# dual_sampler.net
KiCad netlist of a schematic drawn in EAGLE
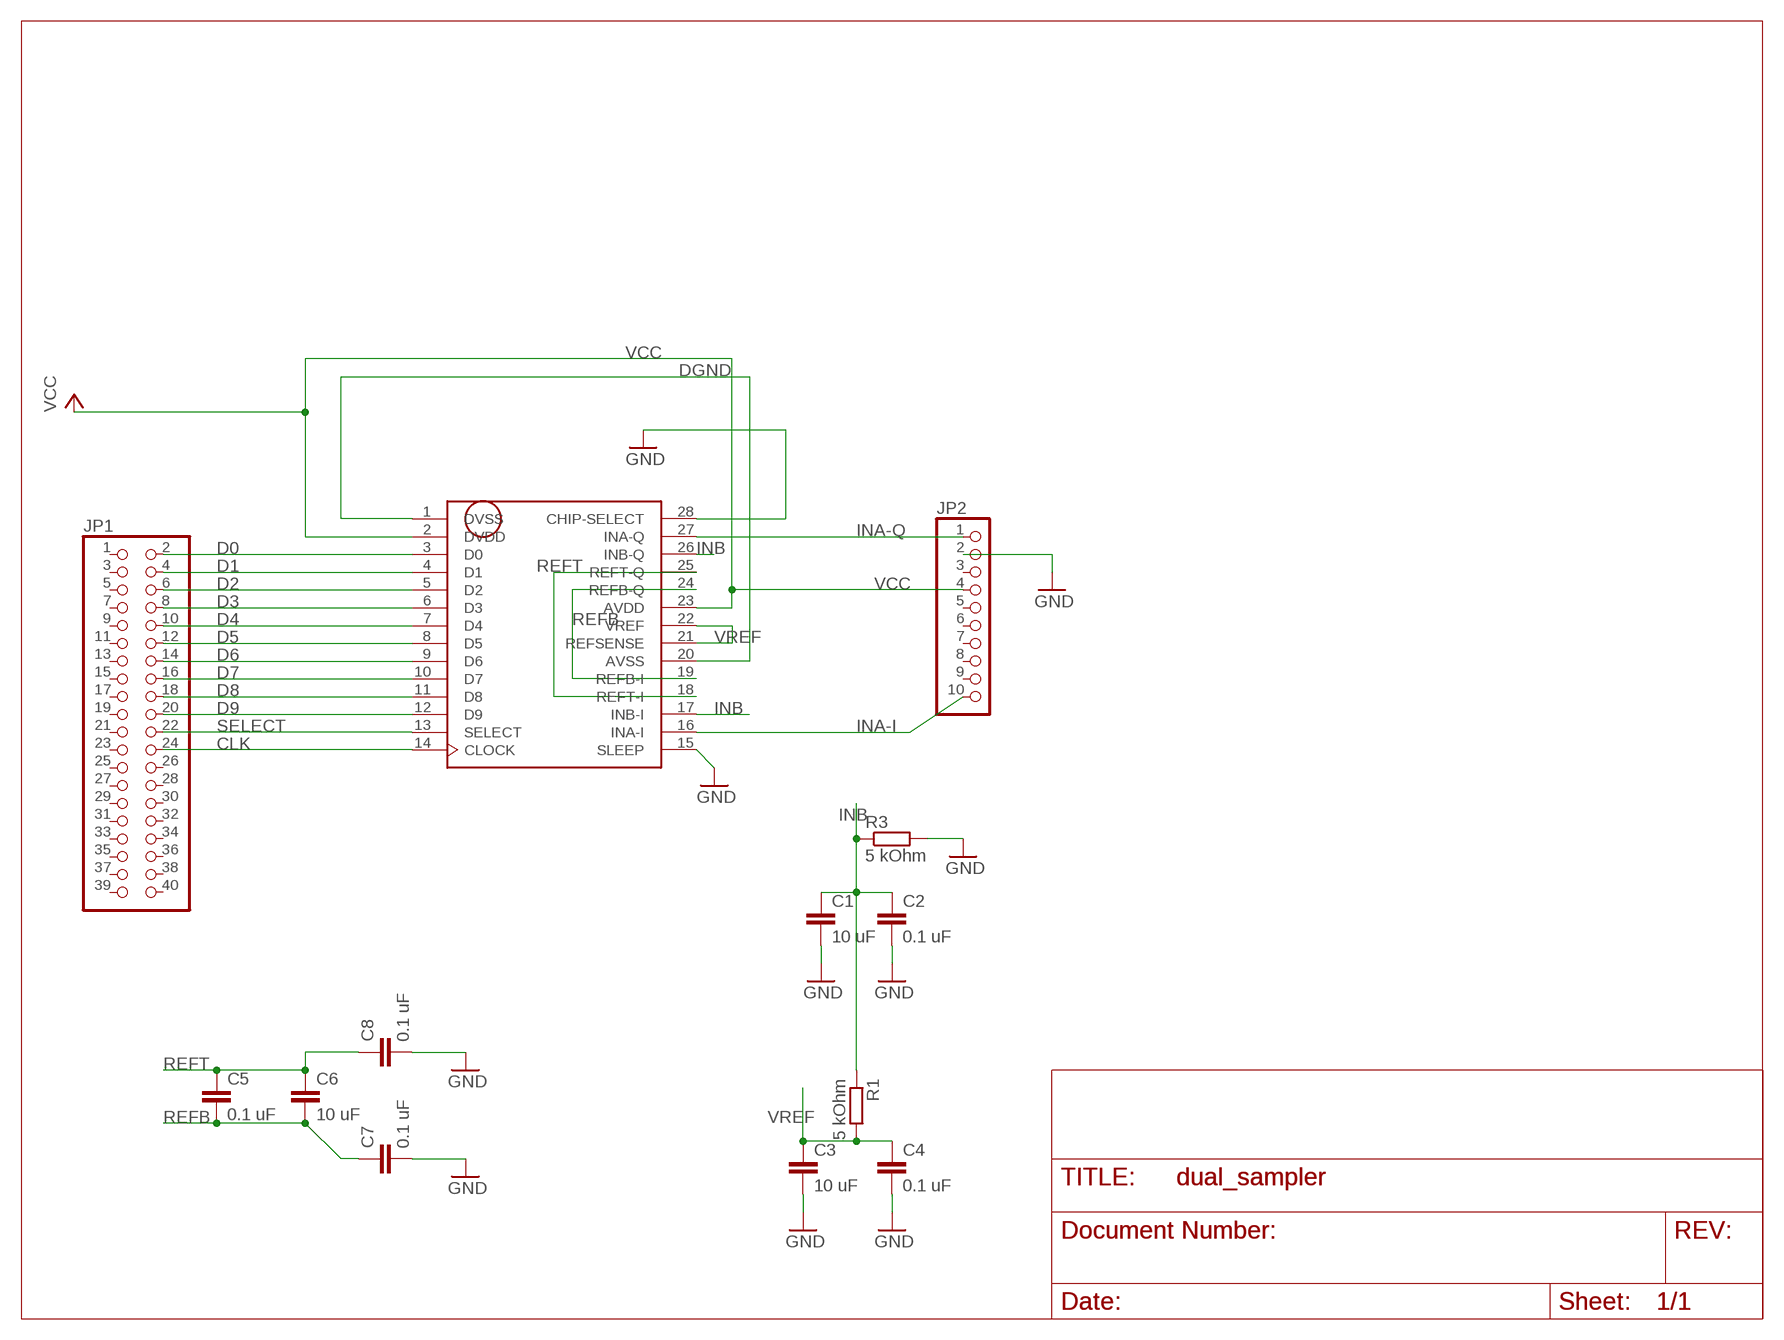
[diagram p0: schematic, sheet 1]

(export (version "E")
  (design (tool "Eeschema 10.0.6"))
  (components
    (comp (ref "C1")
      (value "10 uF")
      (footprint "eagle-import:C2.5-3")
      (libsource (lib "eagle-import") (part "C2,5-3"))
    )
    (comp (ref "C2")
      (value "0.1 uF")
      (footprint "eagle-import:C2.5-3")
      (libsource (lib "eagle-import") (part "C2,5-3"))
    )
    (comp (ref "C3")
      (value "10 uF")
      (footprint "eagle-import:C2.5-3")
      (libsource (lib "eagle-import") (part "C2,5-3"))
    )
    (comp (ref "C4")
      (value "0.1 uF")
      (footprint "eagle-import:C2.5-3")
      (libsource (lib "eagle-import") (part "C2,5-3"))
    )
    (comp (ref "C5")
      (value "0.1 uF")
      (footprint "eagle-import:C2.5-3")
      (libsource (lib "eagle-import") (part "C2,5-3"))
    )
    (comp (ref "C6")
      (value "10 uF")
      (footprint "eagle-import:C2.5-3")
      (libsource (lib "eagle-import") (part "C2,5-3"))
    )
    (comp (ref "C7")
      (value "0.1 uF")
      (footprint "eagle-import:C2.5-3")
      (libsource (lib "eagle-import") (part "C2,5-3"))
    )
    (comp (ref "C8")
      (value "0.1 uF")
      (footprint "eagle-import:C2.5-3")
      (libsource (lib "eagle-import") (part "C2,5-3"))
    )
    (comp (ref "JP1")
      (value "PINHD-2X20")
      (footprint "eagle-import:2X20")
      (libsource (lib "eagle-import") (part "PINHD-2X20"))
    )
    (comp (ref "JP2")
      (value "PINHD-1X10")
      (footprint "eagle-import:1X10")
      (libsource (lib "eagle-import") (part "PINHD-1X10"))
    )
    (comp (ref "R1")
      (value "5 kOhm")
      (footprint "eagle-import:0204_7")
      (libsource (lib "eagle-import") (part "R-EU_0204/7"))
    )
    (comp (ref "R3")
      (value "5 kOhm")
      (footprint "eagle-import:0204_7")
      (libsource (lib "eagle-import") (part "R-EU_0204/7"))
    )
    (comp (ref "U$1")
      (value "AD9201ARSZ")
      (footprint "eagle-import:SSOP28")
      (libsource (lib "eagle-import") (part "AD9201ARSZ"))
    )
  )
  (nets
    (net (code "1") (name "/CLK") (class "Default")
      (node (ref "JP1") (pin "24") (pinfunction "24_24") (pintype "passive"))
      (node (ref "U$1") (pin "14") (pinfunction "CLOCK_14") (pintype "input"))
    )
    (net (code "2") (name "/D0") (class "Default")
      (node (ref "JP1") (pin "2") (pinfunction "2_2") (pintype "passive"))
      (node (ref "U$1") (pin "3") (pinfunction "D0_3") (pintype "output"))
    )
    (net (code "3") (name "/D1") (class "Default")
      (node (ref "JP1") (pin "4") (pinfunction "4_4") (pintype "passive"))
      (node (ref "U$1") (pin "4") (pinfunction "D1_4") (pintype "output"))
    )
    (net (code "4") (name "/D2") (class "Default")
      (node (ref "JP1") (pin "6") (pinfunction "6_6") (pintype "passive"))
      (node (ref "U$1") (pin "5") (pinfunction "D2_5") (pintype "output"))
    )
    (net (code "5") (name "/D3") (class "Default")
      (node (ref "JP1") (pin "8") (pinfunction "8_8") (pintype "passive"))
      (node (ref "U$1") (pin "6") (pinfunction "D3_6") (pintype "output"))
    )
    (net (code "6") (name "/D4") (class "Default")
      (node (ref "JP1") (pin "10") (pinfunction "10_10") (pintype "passive"))
      (node (ref "U$1") (pin "7") (pinfunction "D4_7") (pintype "output"))
    )
    (net (code "7") (name "/D5") (class "Default")
      (node (ref "JP1") (pin "12") (pinfunction "12_12") (pintype "passive"))
      (node (ref "U$1") (pin "8") (pinfunction "D5_8") (pintype "output"))
    )
    (net (code "8") (name "/D6") (class "Default")
      (node (ref "JP1") (pin "14") (pinfunction "14_14") (pintype "passive"))
      (node (ref "U$1") (pin "9") (pinfunction "D6_9") (pintype "output"))
    )
    (net (code "9") (name "/D7") (class "Default")
      (node (ref "JP1") (pin "16") (pinfunction "16_16") (pintype "passive"))
      (node (ref "U$1") (pin "10") (pinfunction "D7_10") (pintype "output"))
    )
    (net (code "10") (name "/D8") (class "Default")
      (node (ref "JP1") (pin "18") (pinfunction "18_18") (pintype "passive"))
      (node (ref "U$1") (pin "11") (pinfunction "D8_11") (pintype "output"))
    )
    (net (code "11") (name "/D9") (class "Default")
      (node (ref "JP1") (pin "20") (pinfunction "20_20") (pintype "passive"))
      (node (ref "U$1") (pin "12") (pinfunction "D9_12") (pintype "output"))
    )
    (net (code "12") (name "/DGND") (class "Default")
      (node (ref "U$1") (pin "1") (pinfunction "DVSS_1") (pintype "power_in"))
      (node (ref "U$1") (pin "20") (pinfunction "AVSS_20") (pintype "input"))
    )
    (net (code "13") (name "/INA-I") (class "Default")
      (node (ref "JP2") (pin "10") (pinfunction "10_10") (pintype "passive"))
      (node (ref "U$1") (pin "16") (pinfunction "INA-I_16") (pintype "input"))
    )
    (net (code "14") (name "/INA-Q") (class "Default")
      (node (ref "JP2") (pin "1") (pinfunction "1_1") (pintype "passive"))
      (node (ref "U$1") (pin "27") (pinfunction "INA-Q_27") (pintype "input"))
    )
    (net (code "15") (name "/INB") (class "Default")
      (node (ref "C1") (pin "1") (pinfunction "1_1") (pintype "passive"))
      (node (ref "C2") (pin "1") (pinfunction "1_1") (pintype "passive"))
      (node (ref "R1") (pin "1") (pinfunction "1_1") (pintype "passive"))
      (node (ref "R3") (pin "1") (pinfunction "1_1") (pintype "passive"))
      (node (ref "U$1") (pin "17") (pinfunction "INB-I_17") (pintype "input"))
      (node (ref "U$1") (pin "26") (pinfunction "INB-Q_26") (pintype "input"))
    )
    (net (code "16") (name "/REFB") (class "Default")
      (node (ref "C5") (pin "2") (pinfunction "2_2") (pintype "passive"))
      (node (ref "C6") (pin "2") (pinfunction "2_2") (pintype "passive"))
      (node (ref "C7") (pin "1") (pinfunction "1_1") (pintype "passive"))
      (node (ref "U$1") (pin "19") (pinfunction "REFB-I_19") (pintype "bidirectional"))
      (node (ref "U$1") (pin "24") (pinfunction "REFB-Q_24") (pintype "input"))
    )
    (net (code "17") (name "/REFT") (class "Default")
      (node (ref "C5") (pin "1") (pinfunction "1_1") (pintype "passive"))
      (node (ref "C6") (pin "1") (pinfunction "1_1") (pintype "passive"))
      (node (ref "C8") (pin "1") (pinfunction "1_1") (pintype "passive"))
      (node (ref "U$1") (pin "18") (pinfunction "REFT-I_18") (pintype "input"))
      (node (ref "U$1") (pin "25") (pinfunction "REFT-Q_25") (pintype "input"))
    )
    (net (code "18") (name "/SELECT") (class "Default")
      (node (ref "JP1") (pin "22") (pinfunction "22_22") (pintype "passive"))
      (node (ref "U$1") (pin "13") (pinfunction "SELECT_13") (pintype "input"))
    )
    (net (code "19") (name "/VREF") (class "Default")
      (node (ref "C3") (pin "1") (pinfunction "1_1") (pintype "passive"))
      (node (ref "C4") (pin "1") (pinfunction "1_1") (pintype "passive"))
      (node (ref "R1") (pin "2") (pinfunction "2_2") (pintype "passive"))
      (node (ref "U$1") (pin "21") (pinfunction "REFSENSE_21") (pintype "input"))
      (node (ref "U$1") (pin "22") (pinfunction "VREF_22") (pintype "input"))
    )
    (net (code "20") (name "GND") (class "Default")
      (node (ref "C1") (pin "2") (pinfunction "2_2") (pintype "passive"))
      (node (ref "C2") (pin "2") (pinfunction "2_2") (pintype "passive"))
      (node (ref "C3") (pin "2") (pinfunction "2_2") (pintype "passive"))
      (node (ref "C4") (pin "2") (pinfunction "2_2") (pintype "passive"))
      (node (ref "C7") (pin "2") (pinfunction "2_2") (pintype "passive"))
      (node (ref "C8") (pin "2") (pinfunction "2_2") (pintype "passive"))
      (node (ref "JP2") (pin "2") (pinfunction "2_2") (pintype "passive"))
      (node (ref "R3") (pin "2") (pinfunction "2_2") (pintype "passive"))
      (node (ref "U$1") (pin "15") (pinfunction "SLEEP_15") (pintype "input"))
      (node (ref "U$1") (pin "28") (pinfunction "CHIP-SELECT_28") (pintype "input"))
    )
    (net (code "21") (name "VCC") (class "Default")
      (node (ref "JP2") (pin "4") (pinfunction "4_4") (pintype "passive"))
      (node (ref "U$1") (pin "2") (pinfunction "DVDD_2") (pintype "power_in"))
      (node (ref "U$1") (pin "23") (pinfunction "AVDD_23") (pintype "power_in"))
    )
    (net (code "22") (name "unconnected-(JP1-Pad1)") (class "Default")
      (node (ref "JP1") (pin "1") (pinfunction "1_1") (pintype "passive"))
    )
    (net (code "23") (name "unconnected-(JP1-Pad3)") (class "Default")
      (node (ref "JP1") (pin "3") (pinfunction "3_3") (pintype "passive"))
    )
    (net (code "24") (name "unconnected-(JP1-Pad5)") (class "Default")
      (node (ref "JP1") (pin "5") (pinfunction "5_5") (pintype "passive"))
    )
    (net (code "25") (name "unconnected-(JP1-Pad7)") (class "Default")
      (node (ref "JP1") (pin "7") (pinfunction "7_7") (pintype "passive"))
    )
    (net (code "26") (name "unconnected-(JP1-Pad9)") (class "Default")
      (node (ref "JP1") (pin "9") (pinfunction "9_9") (pintype "passive"))
    )
    (net (code "27") (name "unconnected-(JP1-Pad11)") (class "Default")
      (node (ref "JP1") (pin "11") (pinfunction "11_11") (pintype "passive"))
    )
    (net (code "28") (name "unconnected-(JP1-Pad13)") (class "Default")
      (node (ref "JP1") (pin "13") (pinfunction "13_13") (pintype "passive"))
    )
    (net (code "29") (name "unconnected-(JP1-Pad15)") (class "Default")
      (node (ref "JP1") (pin "15") (pinfunction "15_15") (pintype "passive"))
    )
    (net (code "30") (name "unconnected-(JP1-Pad17)") (class "Default")
      (node (ref "JP1") (pin "17") (pinfunction "17_17") (pintype "passive"))
    )
    (net (code "31") (name "unconnected-(JP1-Pad19)") (class "Default")
      (node (ref "JP1") (pin "19") (pinfunction "19_19") (pintype "passive"))
    )
    (net (code "32") (name "unconnected-(JP1-Pad21)") (class "Default")
      (node (ref "JP1") (pin "21") (pinfunction "21_21") (pintype "passive"))
    )
    (net (code "33") (name "unconnected-(JP1-Pad23)") (class "Default")
      (node (ref "JP1") (pin "23") (pinfunction "23_23") (pintype "passive"))
    )
    (net (code "34") (name "unconnected-(JP1-Pad25)") (class "Default")
      (node (ref "JP1") (pin "25") (pinfunction "25_25") (pintype "passive"))
    )
    (net (code "35") (name "unconnected-(JP1-Pad26)") (class "Default")
      (node (ref "JP1") (pin "26") (pinfunction "26_26") (pintype "passive"))
    )
    (net (code "36") (name "unconnected-(JP1-Pad27)") (class "Default")
      (node (ref "JP1") (pin "27") (pinfunction "27_27") (pintype "passive"))
    )
    (net (code "37") (name "unconnected-(JP1-Pad28)") (class "Default")
      (node (ref "JP1") (pin "28") (pinfunction "28_28") (pintype "passive"))
    )
    (net (code "38") (name "unconnected-(JP1-Pad29)") (class "Default")
      (node (ref "JP1") (pin "29") (pinfunction "29_29") (pintype "passive"))
    )
    (net (code "39") (name "unconnected-(JP1-Pad30)") (class "Default")
      (node (ref "JP1") (pin "30") (pinfunction "30_30") (pintype "passive"))
    )
    (net (code "40") (name "unconnected-(JP1-Pad31)") (class "Default")
      (node (ref "JP1") (pin "31") (pinfunction "31_31") (pintype "passive"))
    )
    (net (code "41") (name "unconnected-(JP1-Pad32)") (class "Default")
      (node (ref "JP1") (pin "32") (pinfunction "32_32") (pintype "passive"))
    )
    (net (code "42") (name "unconnected-(JP1-Pad33)") (class "Default")
      (node (ref "JP1") (pin "33") (pinfunction "33_33") (pintype "passive"))
    )
    (net (code "43") (name "unconnected-(JP1-Pad34)") (class "Default")
      (node (ref "JP1") (pin "34") (pinfunction "34_34") (pintype "passive"))
    )
    (net (code "44") (name "unconnected-(JP1-Pad35)") (class "Default")
      (node (ref "JP1") (pin "35") (pinfunction "35_35") (pintype "passive"))
    )
    (net (code "45") (name "unconnected-(JP1-Pad36)") (class "Default")
      (node (ref "JP1") (pin "36") (pinfunction "36_36") (pintype "passive"))
    )
    (net (code "46") (name "unconnected-(JP1-Pad37)") (class "Default")
      (node (ref "JP1") (pin "37") (pinfunction "37_37") (pintype "passive"))
    )
    (net (code "47") (name "unconnected-(JP1-Pad38)") (class "Default")
      (node (ref "JP1") (pin "38") (pinfunction "38_38") (pintype "passive"))
    )
    (net (code "48") (name "unconnected-(JP1-Pad39)") (class "Default")
      (node (ref "JP1") (pin "39") (pinfunction "39_39") (pintype "passive"))
    )
    (net (code "49") (name "unconnected-(JP1-Pad40)") (class "Default")
      (node (ref "JP1") (pin "40") (pinfunction "40_40") (pintype "passive"))
    )
    (net (code "50") (name "unconnected-(JP2-Pad3)") (class "Default")
      (node (ref "JP2") (pin "3") (pinfunction "3_3") (pintype "passive"))
    )
    (net (code "51") (name "unconnected-(JP2-Pad5)") (class "Default")
      (node (ref "JP2") (pin "5") (pinfunction "5_5") (pintype "passive"))
    )
    (net (code "52") (name "unconnected-(JP2-Pad6)") (class "Default")
      (node (ref "JP2") (pin "6") (pinfunction "6_6") (pintype "passive"))
    )
    (net (code "53") (name "unconnected-(JP2-Pad7)") (class "Default")
      (node (ref "JP2") (pin "7") (pinfunction "7_7") (pintype "passive"))
    )
    (net (code "54") (name "unconnected-(JP2-Pad8)") (class "Default")
      (node (ref "JP2") (pin "8") (pinfunction "8_8") (pintype "passive"))
    )
    (net (code "55") (name "unconnected-(JP2-Pad9)") (class "Default")
      (node (ref "JP2") (pin "9") (pinfunction "9_9") (pintype "passive"))
    )
  )
)
